# SymphonyLights_SOC_v1_2.net
KiCad netlist of a schematic drawn in Altium Designer
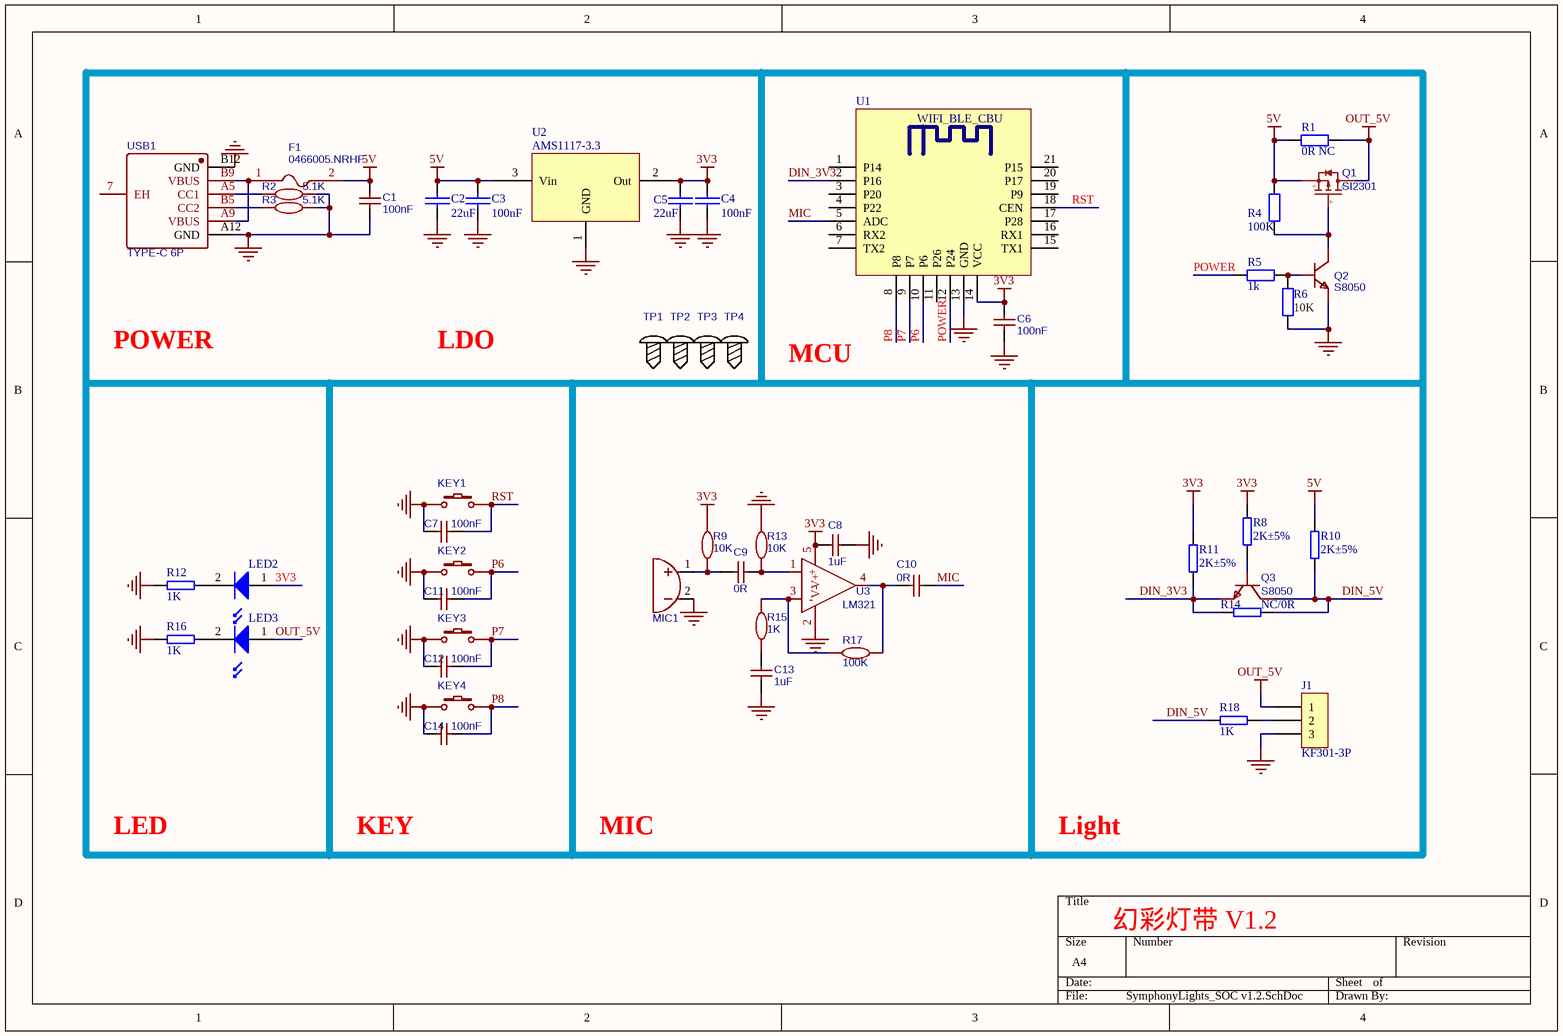
[diagram p0: SymphonyLights_SOC v1.2.SchDoc]

(export (version "E")
  (design (tool "Eeschema 10.0.6"))
  (components
    (comp (ref "C1")
      (value "100nF")
      (footprint "0805C")
      (fields
        (field (name "BOM_MANUFACTURER PART") "0805B104K500NT")
        (field (name "BOM_SUPPLIER PART") "C38141")
      )
      (libsource (lib "altium-import") (part "root_1_100nF_"))
    )
    (comp (ref "C2")
      (value "22uF")
      (footprint "0805C")
      (description "Capacitor")
      (libsource (lib "昊华元件库sch") (part "CAP"))
    )
    (comp (ref "C3")
      (value "100nF")
      (footprint "0805C")
      (description "Capacitor")
      (libsource (lib "昊华元件库sch") (part "CAP"))
    )
    (comp (ref "C4")
      (value "100nF")
      (footprint "0805C")
      (description "Capacitor")
      (libsource (lib "昊华元件库sch") (part "CAP"))
    )
    (comp (ref "C5")
      (value "22uF")
      (footprint "0805C")
      (description "Capacitor")
      (libsource (lib "昊华元件库sch") (part "CAP"))
    )
    (comp (ref "C6")
      (value "100nF")
      (footprint "0805C")
      (fields
        (field (name "BOM_MANUFACTURER PART") "0805B104K500NT")
        (field (name "BOM_SUPPLIER PART") "C38141")
      )
      (libsource (lib "altium-import") (part "root_1_100nF_"))
    )
    (comp (ref "C7")
      (value "100nF")
      (footprint "0805C")
      (fields
        (field (name "BOM_MANUFACTURER PART") "0805B104K500NT")
        (field (name "BOM_SUPPLIER PART") "C38141")
      )
      (libsource (lib "altium-import") (part "root_0_100nF_"))
    )
    (comp (ref "C8")
      (value "1uF")
      (footprint "0805C")
      (fields
        (field (name "BOM_MANUFACTURER PART") "0805B104K500NT")
        (field (name "BOM_SUPPLIER PART") "C38141")
      )
      (libsource (lib "altium-import") (part "root_0_100nF_"))
    )
    (comp (ref "C9")
      (value "0R")
      (footprint "0805C")
      (fields
        (field (name "BOM_MANUFACTURER PART") "0805B104K500NT")
        (field (name "BOM_SUPPLIER PART") "C38141")
      )
      (libsource (lib "altium-import") (part "root_2_100nF_"))
    )
    (comp (ref "C10")
      (value "0R")
      (footprint "0805C")
      (fields
        (field (name "BOM_MANUFACTURER PART") "0805B104K500NT")
        (field (name "BOM_SUPPLIER PART") "C38141")
      )
      (libsource (lib "altium-import") (part "root_2_100nF_"))
    )
    (comp (ref "C11")
      (value "100nF")
      (footprint "0805C")
      (fields
        (field (name "BOM_MANUFACTURER PART") "0805B104K500NT")
        (field (name "BOM_SUPPLIER PART") "C38141")
      )
      (libsource (lib "altium-import") (part "root_0_100nF_"))
    )
    (comp (ref "C12")
      (value "100nF")
      (footprint "0805C")
      (fields
        (field (name "BOM_MANUFACTURER PART") "0805B104K500NT")
        (field (name "BOM_SUPPLIER PART") "C38141")
      )
      (libsource (lib "altium-import") (part "root_0_100nF_"))
    )
    (comp (ref "C13")
      (value "1uF")
      (footprint "0805C")
      (fields
        (field (name "BOM_MANUFACTURER PART") "0805B104K500NT")
        (field (name "BOM_SUPPLIER PART") "C38141")
      )
      (libsource (lib "altium-import") (part "root_3_100nF_"))
    )
    (comp (ref "C14")
      (value "100nF")
      (footprint "0805C")
      (fields
        (field (name "BOM_MANUFACTURER PART") "0805B104K500NT")
        (field (name "BOM_SUPPLIER PART") "C38141")
      )
      (libsource (lib "altium-import") (part "root_0_100nF_"))
    )
    (comp (ref "F1")
      (value "0466005.NRHF")
      (footprint "1206F")
      (fields (field (name "BOM_SUPPLIER PART") "C57525"))
      (libsource (lib "altium-import") (part "root_0_0466005.NRHF_"))
    )
    (comp (ref "J1")
      (value "KF301-3P")
      (footprint "SIP3 - 2.54")
      (description "Connector")
      (libsource (lib "小马元件库sch") (part "CON3"))
    )
    (comp (ref "KEY1")
      (value "RESET")
      (footprint "KEY-SMD_4P-L7.8-W2.8-P4.20-EH")
      (fields
        (field (name "BOM_SUPPLIER PART") "C118141")
        (field (name "BOM_MANUFACTURER PART") "K2-1107ST-A4SW-06")
        (field (name "CONTRIBUTOR") "LCEDA_Lib")
      )
      (libsource (lib "altium-import") (part "root_2_mirrored__"))
    )
    (comp (ref "KEY2")
      (value "场景")
      (footprint "KEY-SMD_4P-L7.8-W2.8-P4.20-EH")
      (fields
        (field (name "BOM_SUPPLIER PART") "C118141")
        (field (name "BOM_MANUFACTURER PART") "K2-1107ST-A4SW-06")
        (field (name "CONTRIBUTOR") "LCEDA_Lib")
      )
      (libsource (lib "altium-import") (part "root_2_mirrored__"))
    )
    (comp (ref "KEY3")
      (value "音乐")
      (footprint "KEY-SMD_4P-L7.8-W2.8-P4.20-EH")
      (fields
        (field (name "BOM_SUPPLIER PART") "C118141")
        (field (name "BOM_MANUFACTURER PART") "K2-1107ST-A4SW-06")
        (field (name "CONTRIBUTOR") "LCEDA_Lib")
      )
      (libsource (lib "altium-import") (part "root_2_mirrored__"))
    )
    (comp (ref "KEY4")
      (value "开关")
      (footprint "KEY-SMD_4P-L7.8-W2.8-P4.20-EH")
      (fields
        (field (name "BOM_SUPPLIER PART") "C118141")
        (field (name "BOM_MANUFACTURER PART") "K2-1107ST-A4SW-06")
        (field (name "CONTRIBUTOR") "LCEDA_Lib")
      )
      (libsource (lib "altium-import") (part "root_2_mirrored__"))
    )
    (comp (ref "LED2")
      (value "LED")
      (footprint "0805LED")
      (fields (field (name "PUBLISHER") "*"))
      (libsource (lib "小马元件库sch") (part "LED"))
    )
    (comp (ref "LED3")
      (value "LED")
      (footprint "0805LED")
      (fields (field (name "PUBLISHER") "*"))
      (libsource (lib "小马元件库sch") (part "LED"))
    )
    (comp (ref "MIC1")
      (value "GMI6050P-66DB")
      (footprint "MIC-TH_BD6.0-P1.90-D0.4-L-RD")
      (fields (field (name "BOM_SUPPLIER PART") "C233954") (field (name "CONTRIBUTOR") "LCSC"))
      (libsource (lib "altium-import") (part "root_3_mirrored_GMI6050P-66DB_"))
    )
    (comp (ref "Q1")
      (value "SI2301")
      (footprint "SOT-23(SOT-23-3)")
      (fields (field (name "BOM_SUPPLIER PART") "C181086") (field (name "CONTRIBUTOR") "lengyuefeng"))
      (libsource (lib "altium-import") (part "root_1_mirrored_SI2301_"))
    )
    (comp (ref "Q2")
      (value "S8050")
      (footprint "SOT-23(SOT-23-3)")
      (fields (field (name "BOM_SUPPLIER PART") "C2146"))
      (libsource (lib "altium-import") (part "root_0_S8050_"))
    )
    (comp (ref "Q3")
      (value "S8050")
      (footprint "SOT-23(SOT-23-3)")
      (fields (field (name "BOM_SUPPLIER PART") "C2146"))
      (libsource (lib "altium-import") (part "root_3_S8050_"))
    )
    (comp (ref "R1")
      (value "0R NC")
      (footprint "0805R")
      (description "Resistor")
      (fields (field (name "PUBLISHER") "Altium Limited"))
      (libsource (lib "") (part "Res2_2"))
    )
    (comp (ref "R2")
      (value "5.1K")
      (footprint "0805R")
      (fields
        (field (name "BOM_SUPPLIER PART") "C328298")
        (field (name "BOM_MANUFACTURER PART") "AECR0402F10K0K9")
        (field (name "CONTRIBUTOR") "LCSC")
      )
      (libsource (lib "altium-import") (part "root_0_10K_"))
    )
    (comp (ref "R3")
      (value "5.1K")
      (footprint "0805R")
      (fields
        (field (name "BOM_SUPPLIER PART") "C328298")
        (field (name "BOM_MANUFACTURER PART") "AECR0402F10K0K9")
        (field (name "CONTRIBUTOR") "LCSC")
      )
      (libsource (lib "altium-import") (part "root_0_10K_"))
    )
    (comp (ref "R4")
      (value "100K")
      (footprint "0805R")
      (description "Resistor")
      (fields (field (name "PUBLISHER") "Altium Limited"))
      (libsource (lib "*") (part "Res2"))
    )
    (comp (ref "R5")
      (value "1k")
      (footprint "0805R")
      (description "Resistor")
      (fields (field (name "PUBLISHER") "Altium Limited"))
      (libsource (lib "") (part "Res2_2"))
    )
    (comp (ref "R6")
      (value "10K")
      (footprint "0805R")
      (description "Resistor")
      (fields (field (name "PUBLISHER") "Altium Limited"))
      (libsource (lib "") (part "Res2_1"))
    )
    (comp (ref "R8") (value "2K±5%") (footprint "0805R") (libsource (lib "昊华元件库sch") (part "RES5")))
    (comp (ref "R9")
      (value "10K")
      (footprint "0805R")
      (fields
        (field (name "BOM_SUPPLIER PART") "C328298")
        (field (name "BOM_MANUFACTURER PART") "AECR0402F10K0K9")
        (field (name "CONTRIBUTOR") "LCSC")
      )
      (libsource (lib "altium-import") (part "root_3_10K_"))
    )
    (comp (ref "R10") (value "2K±5%") (footprint "0805R") (libsource (lib "昊华元件库sch") (part "RES5")))
    (comp (ref "R11") (value "2K±5%") (footprint "0805R") (libsource (lib "昊华元件库sch") (part "RES5")))
    (comp (ref "R12") (value "1K") (footprint "0805R") (libsource (lib "昊华元件库sch") (part "RES5")))
    (comp (ref "R13")
      (value "10K")
      (footprint "0805R")
      (fields
        (field (name "BOM_SUPPLIER PART") "C328298")
        (field (name "BOM_MANUFACTURER PART") "AECR0402F10K0K9")
        (field (name "CONTRIBUTOR") "LCSC")
      )
      (libsource (lib "altium-import") (part "root_3_10K_"))
    )
    (comp (ref "R14") (value "NC/0R") (footprint "0805R") (libsource (lib "昊华元件库sch") (part "RES5")))
    (comp (ref "R15")
      (value "1K")
      (footprint "0805R")
      (fields
        (field (name "BOM_SUPPLIER PART") "C328298")
        (field (name "BOM_MANUFACTURER PART") "AECR0402F10K0K9")
        (field (name "CONTRIBUTOR") "LCSC")
      )
      (libsource (lib "altium-import") (part "root_1_10K_"))
    )
    (comp (ref "R16") (value "1K") (footprint "0805R") (libsource (lib "昊华元件库sch") (part "RES5")))
    (comp (ref "R17")
      (value "100K")
      (footprint "0805R")
      (fields
        (field (name "BOM_SUPPLIER PART") "C328298")
        (field (name "BOM_MANUFACTURER PART") "AECR0402F10K0K9")
        (field (name "CONTRIBUTOR") "LCSC")
      )
      (libsource (lib "altium-import") (part "root_0_10K_"))
    )
    (comp (ref "R18") (value "1K") (footprint "0805R") (libsource (lib "昊华元件库sch") (part "RES5")))
    (comp (ref "TP1")
      (value "~")
      (footprint "M3螺丝孔")
      (fields (field (name "CONTRIBUTOR") "455553Z"))
      (libsource (lib "altium-import") (part "root_0__"))
    )
    (comp (ref "TP2")
      (value "~")
      (footprint "M3螺丝孔")
      (fields (field (name "CONTRIBUTOR") "455553Z"))
      (libsource (lib "altium-import") (part "root_0__"))
    )
    (comp (ref "TP3")
      (value "~")
      (footprint "M3螺丝孔")
      (fields (field (name "CONTRIBUTOR") "455553Z"))
      (libsource (lib "altium-import") (part "root_0__"))
    )
    (comp (ref "TP4")
      (value "~")
      (footprint "M3螺丝孔")
      (fields (field (name "CONTRIBUTOR") "455553Z"))
      (libsource (lib "altium-import") (part "root_0__"))
    )
    (comp (ref "U1")
      (value "WIFI_BLE_CBU")
      (footprint "WIFI_BLE_CBU")
      (description "Module")
      (libsource (lib "TYModeSchlib V03") (part "WIFI_BLE_CBU"))
    )
    (comp (ref "U2") (value "AMS1117-3.3") (footprint "SOT-223") (libsource (lib "mylib") (part "GM1117")))
    (comp (ref "U3")
      (value "LM321")
      (footprint "SOT-23-5")
      (fields (field (name "CONTRIBUTOR") "KiCAD"))
      (libsource (lib "altium-import") (part "root_0_LM321_"))
    )
    (comp (ref "USB1")
      (value "TYPE-C 6P")
      (footprint "TYPE-C-SMD_TYPE-C-6P")
      (fields
        (field (name "BOM_SUPPLIER PART") "C668623")
        (field (name "BOM_MANUFACTURER PART") "TYPE-C 6P(073)")
        (field (name "CONTRIBUTOR") "LCSC")
      )
      (libsource (lib "altium-import") (part "root_0_mirrored_TYPE-C 6P(073)_"))
    )
  )
  (nets
    (net (code "1") (name "/DIN_3V3") (class "Default")
      (node (ref "Q3") (pin "2") (pinfunction "E_2") (pintype "passive"))
      (node (ref "R11") (pin "2") (pinfunction "2_2") (pintype "passive"))
      (node (ref "R14") (pin "1") (pinfunction "1_1") (pintype "passive"))
      (node (ref "U1") (pin "2") (pinfunction "P16_2") (pintype "passive"))
    )
    (net (code "2") (name "/DIN_5V") (class "Default")
      (node (ref "Q3") (pin "3") (pinfunction "C_3") (pintype "passive"))
      (node (ref "R10") (pin "2") (pinfunction "2_2") (pintype "passive"))
      (node (ref "R14") (pin "2") (pinfunction "2_2") (pintype "passive"))
      (node (ref "R18") (pin "1") (pinfunction "1_1") (pintype "passive"))
    )
    (net (code "3") (name "/MIC") (class "Default")
      (node (ref "C10") (pin "1") (pinfunction "1_1") (pintype "passive"))
      (node (ref "U1") (pin "5") (pinfunction "ADC_5") (pintype "passive"))
    )
    (net (code "4") (name "/P6") (class "Default")
      (node (ref "C11") (pin "2") (pinfunction "2_2") (pintype "passive"))
      (node (ref "KEY2") (pin "1") (pinfunction "1_1") (pintype "passive"))
      (node (ref "U1") (pin "10") (pinfunction "P6_10") (pintype "passive"))
    )
    (net (code "5") (name "/P7") (class "Default")
      (node (ref "C12") (pin "2") (pinfunction "2_2") (pintype "passive"))
      (node (ref "KEY3") (pin "1") (pinfunction "1_1") (pintype "passive"))
      (node (ref "U1") (pin "9") (pinfunction "P7_9") (pintype "passive"))
    )
    (net (code "6") (name "/P8") (class "Default")
      (node (ref "C14") (pin "2") (pinfunction "2_2") (pintype "passive"))
      (node (ref "KEY4") (pin "1") (pinfunction "1_1") (pintype "passive"))
      (node (ref "U1") (pin "8") (pinfunction "P8_8") (pintype "passive"))
    )
    (net (code "7") (name "/POWER") (class "Default")
      (node (ref "R5") (pin "1") (pinfunction "1_1") (pintype "passive"))
      (node (ref "U1") (pin "12") (pinfunction "P24_12") (pintype "passive"))
    )
    (net (code "8") (name "/RST") (class "Default")
      (node (ref "C7") (pin "2") (pinfunction "2_2") (pintype "passive"))
      (node (ref "KEY1") (pin "1") (pinfunction "1_1") (pintype "passive"))
      (node (ref "U1") (pin "18") (pinfunction "CEN_18") (pintype "passive"))
    )
    (net (code "9") (name "3V3") (class "Default")
      (node (ref "C4") (pin "1") (pinfunction "1_1") (pintype "passive"))
      (node (ref "C5") (pin "1") (pinfunction "1_1") (pintype "passive"))
      (node (ref "C6") (pin "2") (pinfunction "2_2") (pintype "passive"))
      (node (ref "C8") (pin "1") (pinfunction "1_1") (pintype "passive"))
      (node (ref "LED2") (pin "1") (pinfunction "1_1") (pintype "passive"))
      (node (ref "R11") (pin "1") (pinfunction "1_1") (pintype "passive"))
      (node (ref "R8") (pin "1") (pinfunction "1_1") (pintype "passive"))
      (node (ref "R9") (pin "1") (pinfunction "1_1") (pintype "passive"))
      (node (ref "U1") (pin "14") (pinfunction "VCC_14") (pintype "passive"))
      (node (ref "U2") (pin "2") (pinfunction "Out_2") (pintype "passive"))
      (node (ref "U3") (pin "5") (pinfunction "V+_5") (pintype "passive"))
    )
    (net (code "10") (name "5V") (class "Default")
      (node (ref "C1") (pin "2") (pinfunction "2_2") (pintype "passive"))
      (node (ref "C2") (pin "1") (pinfunction "1_1") (pintype "passive"))
      (node (ref "C3") (pin "1") (pinfunction "1_1") (pintype "passive"))
      (node (ref "F1") (pin "2") (pinfunction "2_2") (pintype "passive"))
      (node (ref "Q1") (pin "2") (pinfunction "S_2") (pintype "passive"))
      (node (ref "R1") (pin "1") (pinfunction "1_1") (pintype "passive"))
      (node (ref "R10") (pin "1") (pinfunction "1_1") (pintype "passive"))
      (node (ref "R4") (pin "2") (pinfunction "2_2") (pintype "passive"))
      (node (ref "U2") (pin "3") (pinfunction "Vin_3") (pintype "passive"))
    )
    (net (code "11") (name "GND") (class "Default")
      (node (ref "C1") (pin "1") (pinfunction "1_1") (pintype "passive"))
      (node (ref "C11") (pin "1") (pinfunction "1_1") (pintype "passive"))
      (node (ref "C12") (pin "1") (pinfunction "1_1") (pintype "passive"))
      (node (ref "C13") (pin "2") (pinfunction "2_2") (pintype "passive"))
      (node (ref "C14") (pin "1") (pinfunction "1_1") (pintype "passive"))
      (node (ref "C2") (pin "2") (pinfunction "2_2") (pintype "passive"))
      (node (ref "C3") (pin "2") (pinfunction "2_2") (pintype "passive"))
      (node (ref "C4") (pin "2") (pinfunction "2_2") (pintype "passive"))
      (node (ref "C5") (pin "2") (pinfunction "2_2") (pintype "passive"))
      (node (ref "C6") (pin "1") (pinfunction "1_1") (pintype "passive"))
      (node (ref "C7") (pin "1") (pinfunction "1_1") (pintype "passive"))
      (node (ref "C8") (pin "2") (pinfunction "2_2") (pintype "passive"))
      (node (ref "J1") (pin "3") (pinfunction "3_3") (pintype "passive"))
      (node (ref "KEY1") (pin "2") (pinfunction "2_2") (pintype "passive"))
      (node (ref "KEY2") (pin "2") (pinfunction "2_2") (pintype "passive"))
      (node (ref "KEY3") (pin "2") (pinfunction "2_2") (pintype "passive"))
      (node (ref "KEY4") (pin "2") (pinfunction "2_2") (pintype "passive"))
      (node (ref "MIC1") (pin "2") (pinfunction "2_2") (pintype "passive"))
      (node (ref "Q2") (pin "2") (pinfunction "E_2") (pintype "passive"))
      (node (ref "R12") (pin "2") (pinfunction "2_2") (pintype "passive"))
      (node (ref "R13") (pin "1") (pinfunction "1_1") (pintype "passive"))
      (node (ref "R16") (pin "2") (pinfunction "2_2") (pintype "passive"))
      (node (ref "R2") (pin "2") (pinfunction "2_2") (pintype "passive"))
      (node (ref "R3") (pin "2") (pinfunction "2_2") (pintype "passive"))
      (node (ref "R6") (pin "2") (pinfunction "2_2") (pintype "passive"))
      (node (ref "U1") (pin "13") (pinfunction "GND_13") (pintype "passive"))
      (node (ref "U2") (pin "1") (pinfunction "GND_1") (pintype "passive"))
      (node (ref "U3") (pin "2") (pinfunction "V-_2") (pintype "passive"))
      (node (ref "USB1") (pin "A12") (pinfunction "GND_A12") (pintype "passive"))
      (node (ref "USB1") (pin "B12") (pinfunction "GND_B12") (pintype "passive"))
    )
    (net (code "12") (name "Net-(C9-Pad2)") (class "Default")
      (node (ref "C9") (pin "2") (pinfunction "2_2") (pintype "passive"))
      (node (ref "MIC1") (pin "1") (pinfunction "1_1") (pintype "passive"))
      (node (ref "R9") (pin "2") (pinfunction "2_2") (pintype "passive"))
    )
    (net (code "13") (name "Net-(C10-Pad2)") (class "Default")
      (node (ref "C10") (pin "2") (pinfunction "2_2") (pintype "passive"))
      (node (ref "R17") (pin "2") (pinfunction "2_2") (pintype "passive"))
      (node (ref "U3") (pin "4") (pintype "passive"))
    )
    (net (code "14") (name "Net-(C13-Pad1)") (class "Default")
      (node (ref "C13") (pin "1") (pinfunction "1_1") (pintype "passive"))
      (node (ref "R15") (pin "1") (pinfunction "1_1") (pintype "passive"))
    )
    (net (code "15") (name "Net-(F1-Pad1)") (class "Default")
      (node (ref "F1") (pin "1") (pinfunction "1_1") (pintype "passive"))
      (node (ref "USB1") (pin "A9") (pinfunction "VBUS_A9") (pintype "passive"))
      (node (ref "USB1") (pin "B9") (pinfunction "VBUS_B9") (pintype "passive"))
    )
    (net (code "16") (name "Net-(J1-Pad2)") (class "Default")
      (node (ref "J1") (pin "2") (pinfunction "2_2") (pintype "passive"))
      (node (ref "R18") (pin "2") (pinfunction "2_2") (pintype "passive"))
    )
    (net (code "17") (name "Net-(LED2-Pad2)") (class "Default")
      (node (ref "LED2") (pin "2") (pinfunction "2_2") (pintype "passive"))
      (node (ref "R12") (pin "1") (pinfunction "1_1") (pintype "passive"))
    )
    (net (code "18") (name "Net-(LED3-Pad2)") (class "Default")
      (node (ref "LED3") (pin "2") (pinfunction "2_2") (pintype "passive"))
      (node (ref "R16") (pin "1") (pinfunction "1_1") (pintype "passive"))
    )
    (net (code "19") (name "Net-(Q1-G)") (class "Default")
      (node (ref "Q1") (pin "1") (pinfunction "G_1") (pintype "passive"))
      (node (ref "Q2") (pin "3") (pinfunction "C_3") (pintype "passive"))
      (node (ref "R4") (pin "1") (pinfunction "1_1") (pintype "passive"))
    )
    (net (code "20") (name "Net-(Q2-B)") (class "Default")
      (node (ref "Q2") (pin "1") (pinfunction "B_1") (pintype "passive"))
      (node (ref "R5") (pin "2") (pinfunction "2_2") (pintype "passive"))
      (node (ref "R6") (pin "1") (pinfunction "1_1") (pintype "passive"))
    )
    (net (code "21") (name "Net-(Q3-B)") (class "Default")
      (node (ref "Q3") (pin "1") (pinfunction "B_1") (pintype "passive"))
      (node (ref "R8") (pin "2") (pinfunction "2_2") (pintype "passive"))
    )
    (net (code "22") (name "Net-(U3-+)") (class "Default")
      (node (ref "C9") (pin "1") (pinfunction "1_1") (pintype "passive"))
      (node (ref "R13") (pin "2") (pinfunction "2_2") (pintype "passive"))
      (node (ref "U3") (pin "1") (pinfunction "+_1") (pintype "passive"))
    )
    (net (code "23") (name "Net-(U3--)") (class "Default")
      (node (ref "R15") (pin "2") (pinfunction "2_2") (pintype "passive"))
      (node (ref "R17") (pin "1") (pinfunction "1_1") (pintype "passive"))
      (node (ref "U3") (pin "3") (pinfunction "-_3") (pintype "passive"))
    )
    (net (code "24") (name "Net-(USB1-CC1)") (class "Default")
      (node (ref "R2") (pin "1") (pinfunction "1_1") (pintype "passive"))
      (node (ref "USB1") (pin "A5") (pinfunction "CC1_A5") (pintype "passive"))
    )
    (net (code "25") (name "Net-(USB1-CC2)") (class "Default")
      (node (ref "R3") (pin "1") (pinfunction "1_1") (pintype "passive"))
      (node (ref "USB1") (pin "B5") (pinfunction "CC2_B5") (pintype "passive"))
    )
    (net (code "26") (name "OUT_5V") (class "Default")
      (node (ref "J1") (pin "1") (pinfunction "1_1") (pintype "passive"))
      (node (ref "LED3") (pin "1") (pinfunction "1_1") (pintype "passive"))
      (node (ref "Q1") (pin "3") (pinfunction "D_3") (pintype "passive"))
      (node (ref "R1") (pin "2") (pinfunction "2_2") (pintype "passive"))
    )
    (net (code "27") (name "unconnected-(U1-P9-Pad19)") (class "Default")
      (node (ref "U1") (pin "19") (pinfunction "P9_19") (pintype "passive"))
    )
    (net (code "28") (name "unconnected-(U1-P14-Pad1)") (class "Default")
      (node (ref "U1") (pin "1") (pinfunction "P14_1") (pintype "passive"))
    )
    (net (code "29") (name "unconnected-(U1-P15-Pad21)") (class "Default")
      (node (ref "U1") (pin "21") (pinfunction "P15_21") (pintype "passive"))
    )
    (net (code "30") (name "unconnected-(U1-P17-Pad20)") (class "Default")
      (node (ref "U1") (pin "20") (pinfunction "P17_20") (pintype "passive"))
    )
    (net (code "31") (name "unconnected-(U1-P20-Pad3)") (class "Default")
      (node (ref "U1") (pin "3") (pinfunction "P20_3") (pintype "passive"))
    )
    (net (code "32") (name "unconnected-(U1-P22-Pad4)") (class "Default")
      (node (ref "U1") (pin "4") (pinfunction "P22_4") (pintype "passive"))
    )
    (net (code "33") (name "unconnected-(U1-P26-Pad11)") (class "Default")
      (node (ref "U1") (pin "11") (pinfunction "P26_11") (pintype "passive"))
    )
    (net (code "34") (name "unconnected-(U1-P28-Pad17)") (class "Default")
      (node (ref "U1") (pin "17") (pinfunction "P28_17") (pintype "passive"))
    )
    (net (code "35") (name "unconnected-(U1-RX1-Pad16)") (class "Default")
      (node (ref "U1") (pin "16") (pinfunction "RX1_16") (pintype "passive"))
    )
    (net (code "36") (name "unconnected-(U1-RX2-Pad6)") (class "Default")
      (node (ref "U1") (pin "6") (pinfunction "RX2_6") (pintype "passive"))
    )
    (net (code "37") (name "unconnected-(U1-TX1-Pad15)") (class "Default")
      (node (ref "U1") (pin "15") (pinfunction "TX1_15") (pintype "passive"))
    )
    (net (code "38") (name "unconnected-(U1-TX2-Pad7)") (class "Default")
      (node (ref "U1") (pin "7") (pinfunction "TX2_7") (pintype "passive"))
    )
    (net (code "39") (name "unconnected-(USB1-EH-Pad7)") (class "Default")
      (node (ref "USB1") (pin "7") (pinfunction "EH_7") (pintype "passive"))
    )
  )
)
